# 1-Schematic_Mosfet_board.net
KiCad netlist of a schematic drawn in EasyEDA
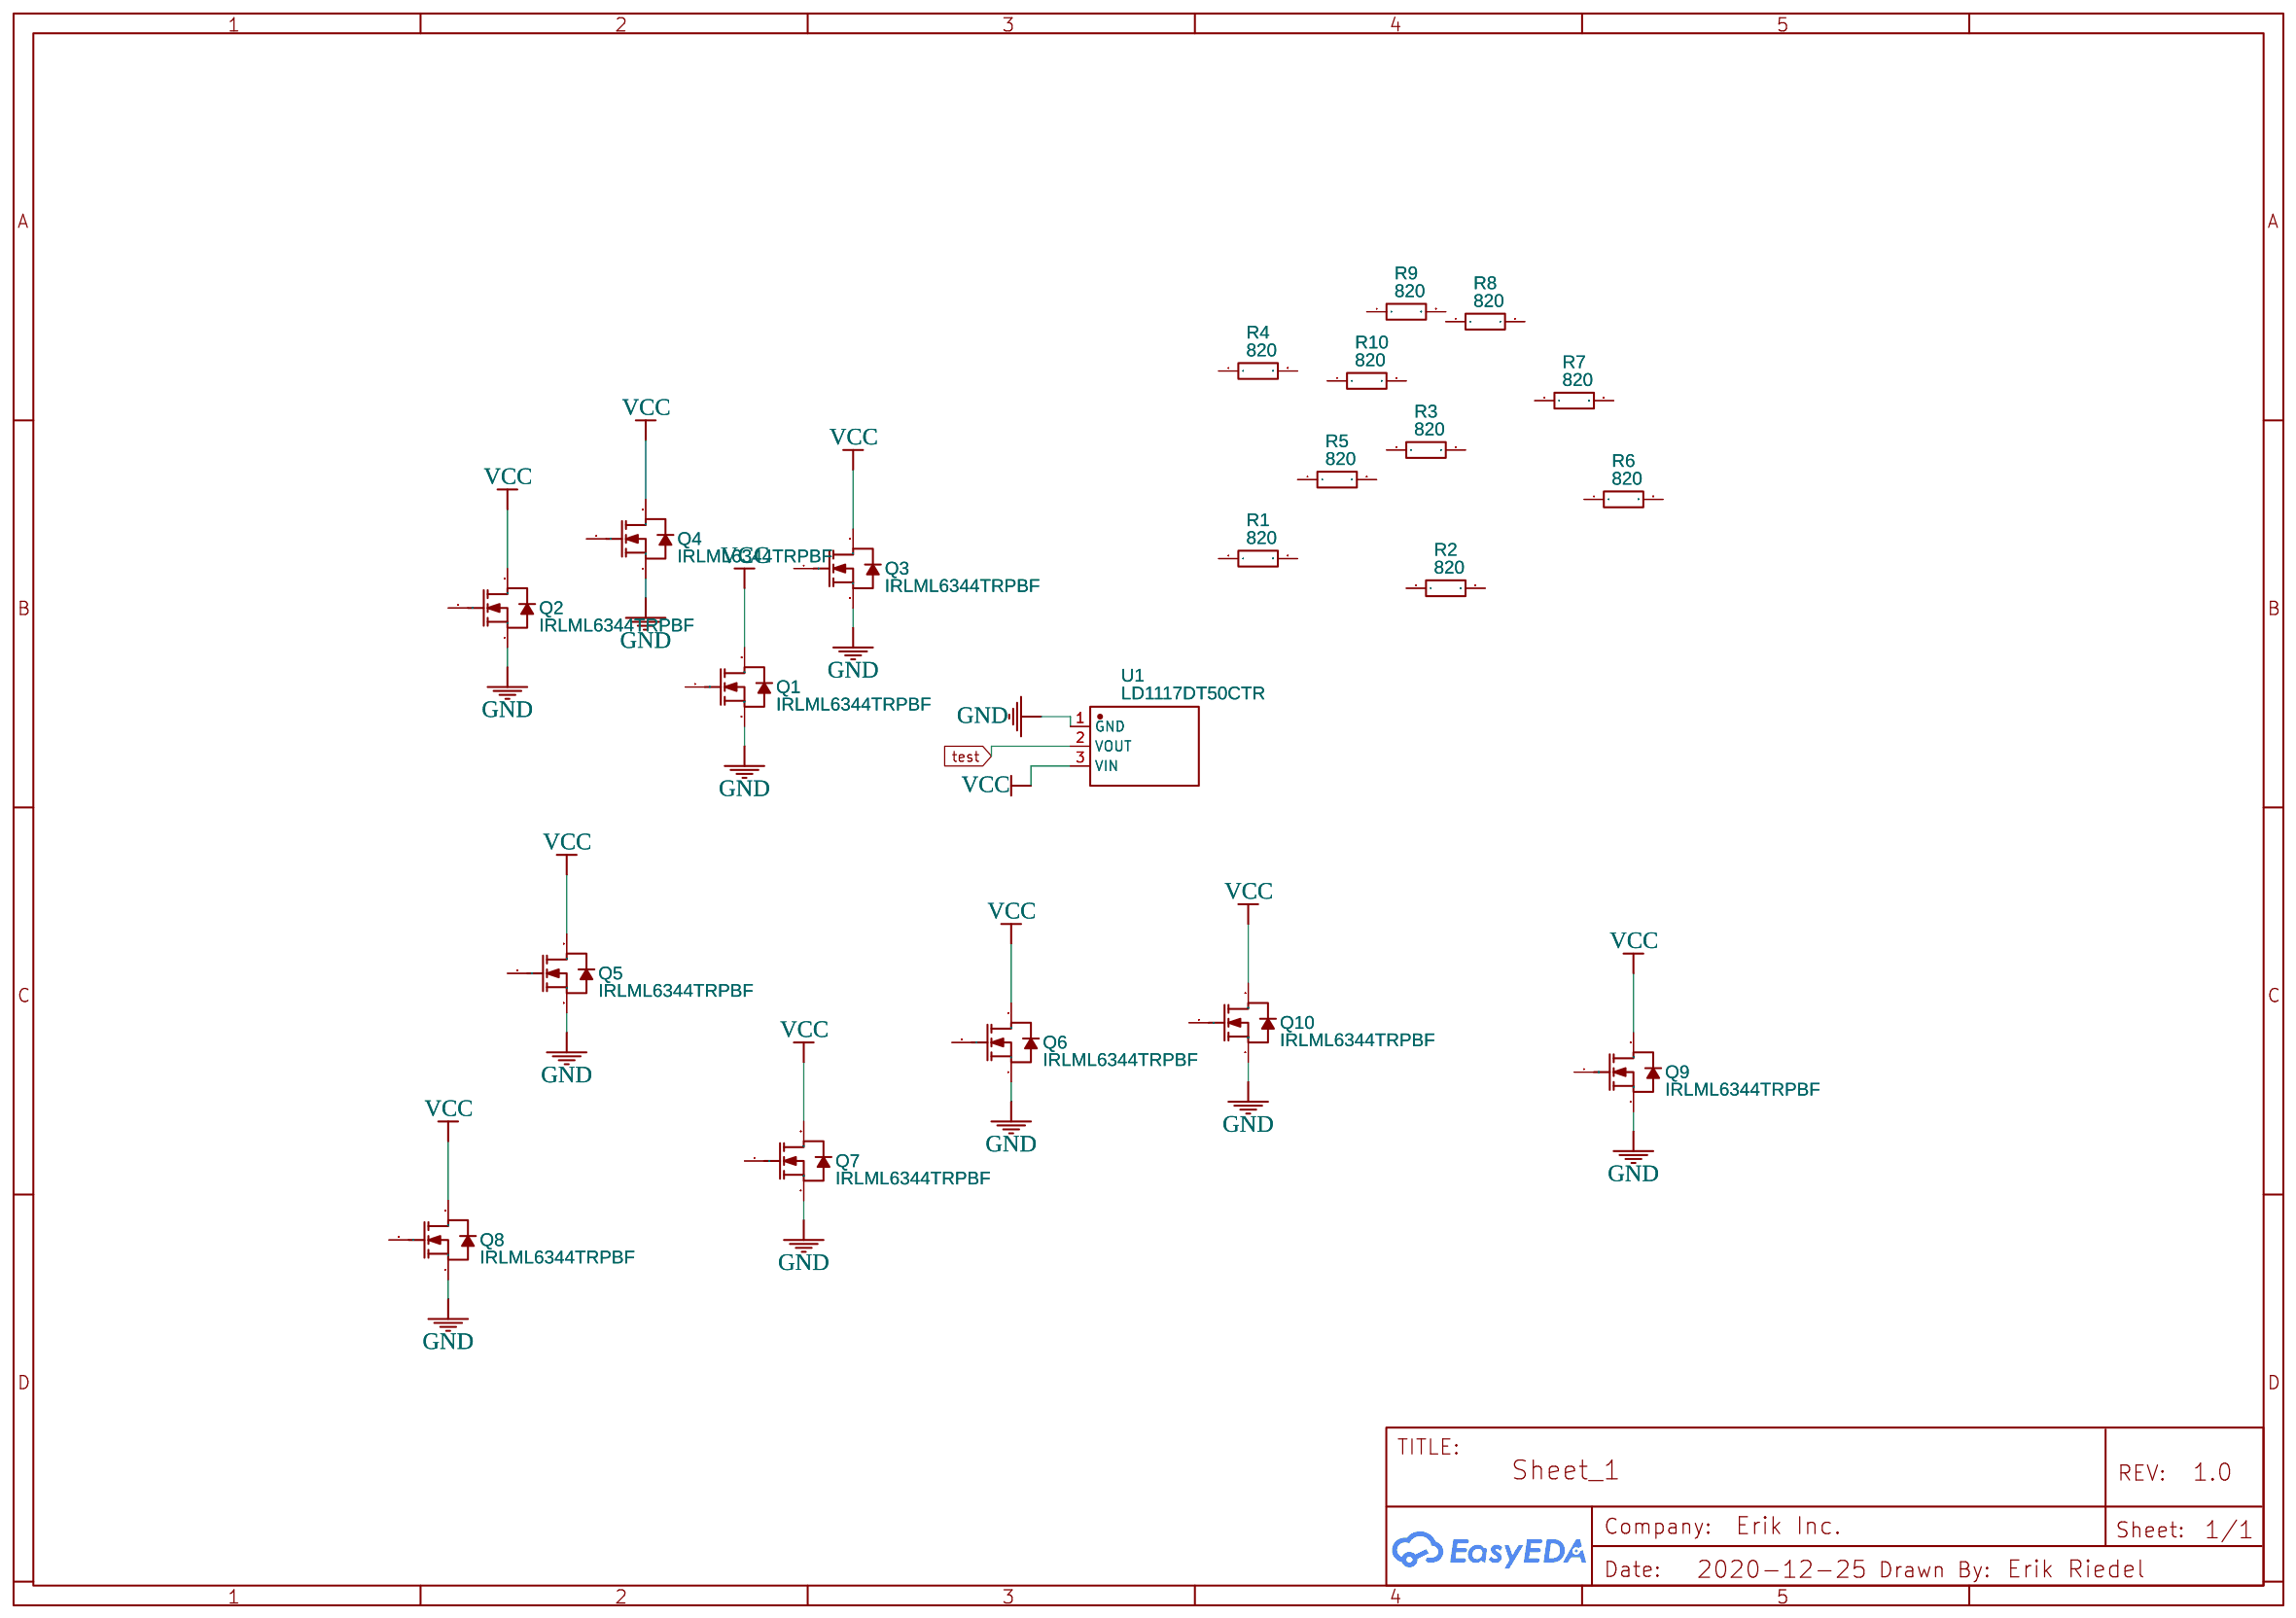
[diagram p0: schematic sheet]

(export (version "E")
  (design (tool "Eeschema 10.0.6"))
  (components
    (comp (ref "Q1")
      (value "IRLML6344TRPBF")
      (fields (field (name "BOM_Supplier Part") "C53550"))
      (libsource (lib "") (part "IRLML6344TRPBF"))
    )
    (comp (ref "Q2")
      (value "IRLML6344TRPBF")
      (fields (field (name "BOM_Supplier Part") "C53550"))
      (libsource (lib "") (part "IRLML6344TRPBF"))
    )
    (comp (ref "Q3")
      (value "IRLML6344TRPBF")
      (fields (field (name "BOM_Supplier Part") "C53550"))
      (libsource (lib "") (part "IRLML6344TRPBF"))
    )
    (comp (ref "Q4")
      (value "IRLML6344TRPBF")
      (fields (field (name "BOM_Supplier Part") "C53550"))
      (libsource (lib "") (part "IRLML6344TRPBF"))
    )
    (comp (ref "Q5")
      (value "IRLML6344TRPBF")
      (fields (field (name "BOM_Supplier Part") "C53550"))
      (libsource (lib "") (part "IRLML6344TRPBF"))
    )
    (comp (ref "Q6")
      (value "IRLML6344TRPBF")
      (fields (field (name "BOM_Supplier Part") "C53550"))
      (libsource (lib "") (part "IRLML6344TRPBF"))
    )
    (comp (ref "Q7")
      (value "IRLML6344TRPBF")
      (fields (field (name "BOM_Supplier Part") "C53550"))
      (libsource (lib "") (part "IRLML6344TRPBF"))
    )
    (comp (ref "Q8")
      (value "IRLML6344TRPBF")
      (fields (field (name "BOM_Supplier Part") "C53550"))
      (libsource (lib "") (part "IRLML6344TRPBF"))
    )
    (comp (ref "Q9")
      (value "IRLML6344TRPBF")
      (fields (field (name "BOM_Supplier Part") "C53550"))
      (libsource (lib "") (part "IRLML6344TRPBF"))
    )
    (comp (ref "Q10")
      (value "IRLML6344TRPBF")
      (fields (field (name "BOM_Supplier Part") "C53550"))
      (libsource (lib "") (part "IRLML6344TRPBF"))
    )
    (comp (ref "R1")
      (value "820")
      (fields
        (field (name "BOM_Manufacturer Part") "0603WAF8200T5E")
        (field (name "BOM_Supplier Part") "C23253")
      )
      (libsource (lib "") (part "0603WAF8200T5E"))
    )
    (comp (ref "R2")
      (value "820")
      (fields
        (field (name "BOM_Manufacturer Part") "0603WAF8200T5E")
        (field (name "BOM_Supplier Part") "C23253")
      )
      (libsource (lib "") (part "0603WAF8200T5E"))
    )
    (comp (ref "R3")
      (value "820")
      (fields
        (field (name "BOM_Manufacturer Part") "0603WAF8200T5E")
        (field (name "BOM_Supplier Part") "C23253")
      )
      (libsource (lib "") (part "0603WAF8200T5E"))
    )
    (comp (ref "R4")
      (value "820")
      (fields
        (field (name "BOM_Manufacturer Part") "0603WAF8200T5E")
        (field (name "BOM_Supplier Part") "C23253")
      )
      (libsource (lib "") (part "0603WAF8200T5E"))
    )
    (comp (ref "R5")
      (value "820")
      (fields
        (field (name "BOM_Manufacturer Part") "0603WAF8200T5E")
        (field (name "BOM_Supplier Part") "C23253")
      )
      (libsource (lib "") (part "0603WAF8200T5E"))
    )
    (comp (ref "R6")
      (value "820")
      (fields
        (field (name "BOM_Manufacturer Part") "0603WAF8200T5E")
        (field (name "BOM_Supplier Part") "C23253")
      )
      (libsource (lib "") (part "0603WAF8200T5E"))
    )
    (comp (ref "R7")
      (value "820")
      (fields
        (field (name "BOM_Manufacturer Part") "0603WAF8200T5E")
        (field (name "BOM_Supplier Part") "C23253")
      )
      (libsource (lib "") (part "0603WAF8200T5E"))
    )
    (comp (ref "R8")
      (value "820")
      (fields
        (field (name "BOM_Manufacturer Part") "0603WAF8200T5E")
        (field (name "BOM_Supplier Part") "C23253")
      )
      (libsource (lib "") (part "0603WAF8200T5E"))
    )
    (comp (ref "R9")
      (value "820")
      (fields
        (field (name "BOM_Manufacturer Part") "0603WAF8200T5E")
        (field (name "BOM_Supplier Part") "C23253")
      )
      (libsource (lib "") (part "0603WAF8200T5E"))
    )
    (comp (ref "R10")
      (value "820")
      (fields
        (field (name "BOM_Manufacturer Part") "0603WAF8200T5E")
        (field (name "BOM_Supplier Part") "C23253")
      )
      (libsource (lib "") (part "0603WAF8200T5E"))
    )
    (comp (ref "U1")
      (value "LD1117DT50CTR")
      (fields (field (name "BOM_Supplier Part") "C93063"))
      (libsource (lib "") (part "LD1117DT50CTR"))
    )
  )
  (nets
    (net (code "1") (name "GND") (class "Default")
      (node (ref "Q1") (pin "2") (pinfunction "S_2") (pintype "unspecified"))
      (node (ref "Q10") (pin "2") (pinfunction "S_2") (pintype "unspecified"))
      (node (ref "Q2") (pin "2") (pinfunction "S_2") (pintype "unspecified"))
      (node (ref "Q3") (pin "2") (pinfunction "S_2") (pintype "unspecified"))
      (node (ref "Q4") (pin "2") (pinfunction "S_2") (pintype "unspecified"))
      (node (ref "Q5") (pin "2") (pinfunction "S_2") (pintype "unspecified"))
      (node (ref "Q6") (pin "2") (pinfunction "S_2") (pintype "unspecified"))
      (node (ref "Q7") (pin "2") (pinfunction "S_2") (pintype "unspecified"))
      (node (ref "Q8") (pin "2") (pinfunction "S_2") (pintype "unspecified"))
      (node (ref "Q9") (pin "2") (pinfunction "S_2") (pintype "unspecified"))
      (node (ref "U1") (pin "1") (pinfunction "GND_1") (pintype "unspecified"))
    )
    (net (code "2") (name "VCC") (class "Default")
      (node (ref "Q1") (pin "3") (pinfunction "D_3") (pintype "unspecified"))
      (node (ref "Q10") (pin "3") (pinfunction "D_3") (pintype "unspecified"))
      (node (ref "Q2") (pin "3") (pinfunction "D_3") (pintype "unspecified"))
      (node (ref "Q3") (pin "3") (pinfunction "D_3") (pintype "unspecified"))
      (node (ref "Q4") (pin "3") (pinfunction "D_3") (pintype "unspecified"))
      (node (ref "Q5") (pin "3") (pinfunction "D_3") (pintype "unspecified"))
      (node (ref "Q6") (pin "3") (pinfunction "D_3") (pintype "unspecified"))
      (node (ref "Q7") (pin "3") (pinfunction "D_3") (pintype "unspecified"))
      (node (ref "Q8") (pin "3") (pinfunction "D_3") (pintype "unspecified"))
      (node (ref "Q9") (pin "3") (pinfunction "D_3") (pintype "unspecified"))
      (node (ref "U1") (pin "3") (pinfunction "VIN_3") (pintype "unspecified"))
    )
    (net (code "3") (name "test") (class "Default")
      (node (ref "U1") (pin "2") (pinfunction "VOUT_2") (pintype "unspecified"))
    )
    (net (code "4") (name "unconnected-(Q1-G-Pad1)") (class "Default")
      (node (ref "Q1") (pin "1") (pinfunction "G_1") (pintype "unspecified"))
    )
    (net (code "5") (name "unconnected-(Q2-G-Pad1)") (class "Default")
      (node (ref "Q2") (pin "1") (pinfunction "G_1") (pintype "unspecified"))
    )
    (net (code "6") (name "unconnected-(Q3-G-Pad1)") (class "Default")
      (node (ref "Q3") (pin "1") (pinfunction "G_1") (pintype "unspecified"))
    )
    (net (code "7") (name "unconnected-(Q4-G-Pad1)") (class "Default")
      (node (ref "Q4") (pin "1") (pinfunction "G_1") (pintype "unspecified"))
    )
    (net (code "8") (name "unconnected-(Q5-G-Pad1)") (class "Default")
      (node (ref "Q5") (pin "1") (pinfunction "G_1") (pintype "unspecified"))
    )
    (net (code "9") (name "unconnected-(Q6-G-Pad1)") (class "Default")
      (node (ref "Q6") (pin "1") (pinfunction "G_1") (pintype "unspecified"))
    )
    (net (code "10") (name "unconnected-(Q7-G-Pad1)") (class "Default")
      (node (ref "Q7") (pin "1") (pinfunction "G_1") (pintype "unspecified"))
    )
    (net (code "11") (name "unconnected-(Q8-G-Pad1)") (class "Default")
      (node (ref "Q8") (pin "1") (pinfunction "G_1") (pintype "unspecified"))
    )
    (net (code "12") (name "unconnected-(Q9-G-Pad1)") (class "Default")
      (node (ref "Q9") (pin "1") (pinfunction "G_1") (pintype "unspecified"))
    )
    (net (code "13") (name "unconnected-(Q10-G-Pad1)") (class "Default")
      (node (ref "Q10") (pin "1") (pinfunction "G_1") (pintype "unspecified"))
    )
    (net (code "14") (name "unconnected-(R1-Pad1)") (class "Default")
      (node (ref "R1") (pin "1") (pinfunction "1_1") (pintype "input"))
    )
    (net (code "15") (name "unconnected-(R1-Pad2)") (class "Default")
      (node (ref "R1") (pin "2") (pinfunction "2_2") (pintype "input"))
    )
    (net (code "16") (name "unconnected-(R2-Pad1)") (class "Default")
      (node (ref "R2") (pin "1") (pinfunction "1_1") (pintype "input"))
    )
    (net (code "17") (name "unconnected-(R2-Pad2)") (class "Default")
      (node (ref "R2") (pin "2") (pinfunction "2_2") (pintype "input"))
    )
    (net (code "18") (name "unconnected-(R3-Pad1)") (class "Default")
      (node (ref "R3") (pin "1") (pinfunction "1_1") (pintype "input"))
    )
    (net (code "19") (name "unconnected-(R3-Pad2)") (class "Default")
      (node (ref "R3") (pin "2") (pinfunction "2_2") (pintype "input"))
    )
    (net (code "20") (name "unconnected-(R4-Pad1)") (class "Default")
      (node (ref "R4") (pin "1") (pinfunction "1_1") (pintype "input"))
    )
    (net (code "21") (name "unconnected-(R4-Pad2)") (class "Default")
      (node (ref "R4") (pin "2") (pinfunction "2_2") (pintype "input"))
    )
    (net (code "22") (name "unconnected-(R5-Pad1)") (class "Default")
      (node (ref "R5") (pin "1") (pinfunction "1_1") (pintype "input"))
    )
    (net (code "23") (name "unconnected-(R5-Pad2)") (class "Default")
      (node (ref "R5") (pin "2") (pinfunction "2_2") (pintype "input"))
    )
    (net (code "24") (name "unconnected-(R6-Pad1)") (class "Default")
      (node (ref "R6") (pin "1") (pinfunction "1_1") (pintype "input"))
    )
    (net (code "25") (name "unconnected-(R6-Pad2)") (class "Default")
      (node (ref "R6") (pin "2") (pinfunction "2_2") (pintype "input"))
    )
    (net (code "26") (name "unconnected-(R7-Pad1)") (class "Default")
      (node (ref "R7") (pin "1") (pinfunction "1_1") (pintype "input"))
    )
    (net (code "27") (name "unconnected-(R7-Pad2)") (class "Default")
      (node (ref "R7") (pin "2") (pinfunction "2_2") (pintype "input"))
    )
    (net (code "28") (name "unconnected-(R8-Pad1)") (class "Default")
      (node (ref "R8") (pin "1") (pinfunction "1_1") (pintype "input"))
    )
    (net (code "29") (name "unconnected-(R8-Pad2)") (class "Default")
      (node (ref "R8") (pin "2") (pinfunction "2_2") (pintype "input"))
    )
    (net (code "30") (name "unconnected-(R9-Pad1)") (class "Default")
      (node (ref "R9") (pin "1") (pinfunction "1_1") (pintype "input"))
    )
    (net (code "31") (name "unconnected-(R9-Pad2)") (class "Default")
      (node (ref "R9") (pin "2") (pinfunction "2_2") (pintype "input"))
    )
    (net (code "32") (name "unconnected-(R10-Pad1)") (class "Default")
      (node (ref "R10") (pin "1") (pinfunction "1_1") (pintype "input"))
    )
    (net (code "33") (name "unconnected-(R10-Pad2)") (class "Default")
      (node (ref "R10") (pin "2") (pinfunction "2_2") (pintype "input"))
    )
  )
)
